# mcu.net
KiCad netlist of a schematic drawn in Altium Designer
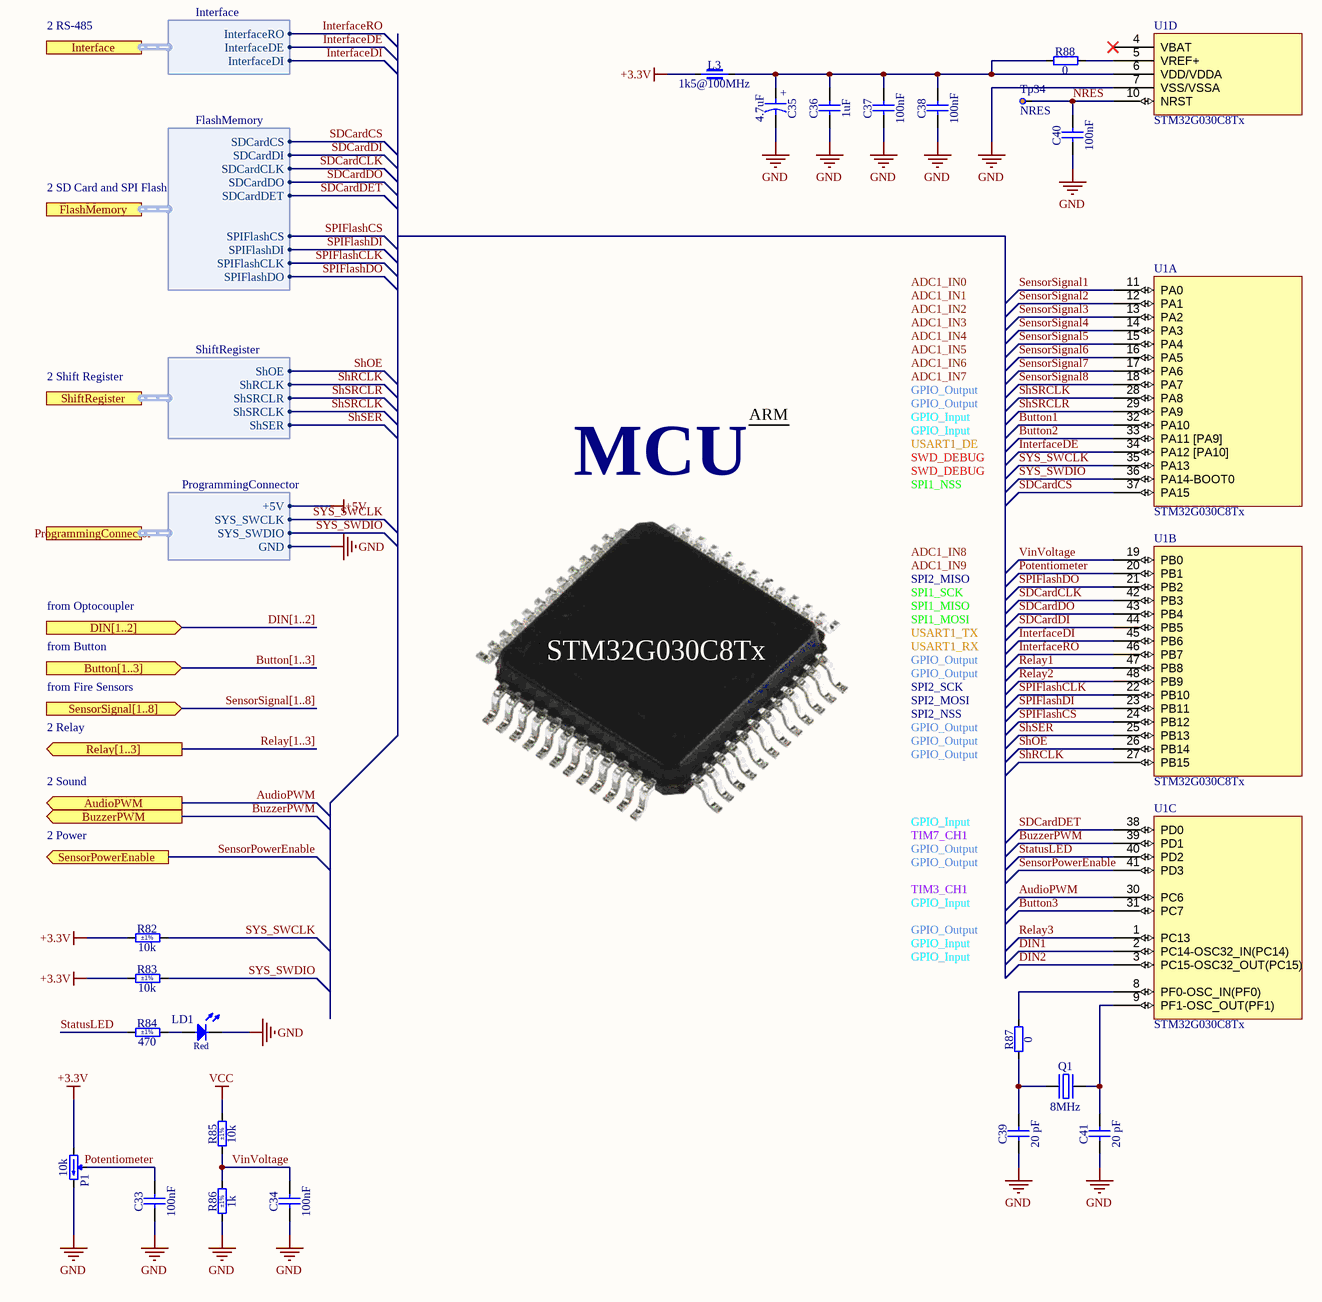
[diagram p0: mcu.SchDoc]

(export (version "E")
  (design (tool "Eeschema 10.0.6"))
  (components
    (comp (ref "C33")
      (value "100nF")
      (footprint "CAPC1608X87N")
      (description "Non-polarised capacitor")
      (fields
        (field (name "PART NUMBER") "CC0603_100NF_50V_10%_X7R")
        (field (name "VOLTAGE") "50V")
        (field (name "AUTHOR") "CERN DEM JLC")
      )
      (libsource (lib "Capacitors") (part "Capacitor - non polarized"))
    )
    (comp (ref "C34")
      (value "100nF")
      (footprint "CAPC1608X87N")
      (description "Non-polarised capacitor")
      (fields
        (field (name "PART NUMBER") "CC0603_100NF_50V_10%_X7R")
        (field (name "VOLTAGE") "50V")
        (field (name "AUTHOR") "CERN DEM JLC")
      )
      (libsource (lib "Capacitors") (part "Capacitor - non polarized"))
    )
    (comp (ref "C35")
      (value "4.7uF")
      (footprint "CAPMP3216X180N")
      (description "Polarised capacitor")
      (fields
        (field (name "PART NUMBER") "CTE3216-18_4.7UF_10V_10%_AVX_TPSA475K010T1400")
        (field (name "VOLTAGE") "10V")
        (field (name "AUTHOR") "CERN DEM JLC")
      )
      (libsource (lib "Capacitors") (part "Capacitor - polarized"))
    )
    (comp (ref "C36")
      (value "1uF")
      (footprint "CAPC1608X87N")
      (description "Non-polarised capacitor")
      (fields
        (field (name "PART NUMBER") "CC0603_1UF_16V_10%_X7R")
        (field (name "VOLTAGE") "16V")
        (field (name "AUTHOR") "CERN DEM JLC")
      )
      (libsource (lib "Capacitors") (part "Capacitor - non polarized"))
    )
    (comp (ref "C37")
      (value "100nF")
      (footprint "CAPC1608X87N")
      (description "Non-polarised capacitor")
      (fields
        (field (name "PART NUMBER") "CC0603_100NF_50V_10%_X7R")
        (field (name "VOLTAGE") "50V")
        (field (name "AUTHOR") "CERN DEM JLC")
      )
      (libsource (lib "Capacitors") (part "Capacitor - non polarized"))
    )
    (comp (ref "C38")
      (value "100nF")
      (footprint "CAPC1608X87N")
      (description "Non-polarised capacitor")
      (fields
        (field (name "PART NUMBER") "CC0603_100NF_50V_10%_X7R")
        (field (name "VOLTAGE") "50V")
        (field (name "AUTHOR") "CERN DEM JLC")
      )
      (libsource (lib "Capacitors") (part "Capacitor - non polarized"))
    )
    (comp (ref "C39")
      (value "20 pF")
      (footprint "CAPC1608X90N")
      (description "Non-polarised capacitor")
      (fields
        (field (name "PART NUMBER") "CC0603_20PF_50V_5%_NP0")
        (field (name "VOLTAGE") "50V")
        (field (name "AUTHOR") "CERN DEM JMW")
      )
      (libsource (lib "Capacitors") (part "Capacitor - non polarized"))
    )
    (comp (ref "C40")
      (value "100nF")
      (footprint "CAPC1608X87N")
      (description "Non-polarised capacitor")
      (fields
        (field (name "PART NUMBER") "CC0603_100NF_50V_10%_X7R")
        (field (name "VOLTAGE") "50V")
        (field (name "AUTHOR") "CERN DEM JLC")
      )
      (libsource (lib "Capacitors") (part "Capacitor - non polarized"))
    )
    (comp (ref "C41")
      (value "20 pF")
      (footprint "CAPC1608X90N")
      (description "Non-polarised capacitor")
      (fields
        (field (name "PART NUMBER") "CC0603_20PF_50V_5%_NP0")
        (field (name "VOLTAGE") "50V")
        (field (name "AUTHOR") "CERN DEM JMW")
      )
      (libsource (lib "Capacitors") (part "Capacitor - non polarized"))
    )
    (comp (ref "L3")
      (value "1k5@100MHz")
      (footprint "INDC2012X110N")
      (fields
        (field (name "PART NUMBER") "IND0805_WURTH_742792097")
        (field (name "POWER") "1A")
        (field (name "TOLERANCE") "±25%")
        (field (name "AUTHOR") "CERN DEM MR")
      )
      (libsource (lib "Inductors & Transformers") (part "Ferrite Bead"))
    )
    (comp (ref "LD1")
      (value "Red")
      (footprint "LED_AVAGO_HSMH-C150")
      (description "LED Red 1C 2A")
      (fields
        (field (name "PART NUMBER") "LED_AVAGO_HSMH-C150")
        (field (name "MANUFACTURER") "AVAGO TECHNOLOGIES")
        (field (name "AUTHOR") "CERN DEM JLC")
      )
      (libsource (lib "ICs And Semiconductors") (part "LED Red 1C 2A"))
    )
    (comp (ref "P1")
      (value "10k")
      (footprint "TRIM_BOURNS_3296W")
      (description "Trimming Potentiometer")
      (fields
        (field (name "PART NUMBER") "TRIM_25T_10K_BOURNS_3296W-1-103LF")
        (field (name "POWER") "0.5W")
        (field (name "AUTHOR") "CERN DEM BC")
      )
      (libsource (lib "Resistors") (part "Trimming Potentiometer"))
    )
    (comp (ref "Q1")
      (value "8MHz")
      (footprint "XTAL_TXC_7A")
      (description "Quartz Crystal")
      (fields
        (field (name "PART NUMBER") "XTAL_8MHZ_TXC_7A-8.000MAAE-T")
        (field (name "MANUFACTURER") "TXC CORPORATION")
        (field (name "AUTHOR") "CERN DEM JLC")
      )
      (libsource (lib "ICs And Semiconductors") (part "Quartz Crystal"))
    )
    (comp (ref "R82")
      (value "10k")
      (footprint "RESC1608X55N")
      (description "Resistor - 1%")
      (fields
        (field (name "TOLERANCE") "±1%")
        (field (name "PART NUMBER") "R0603_10K_1%_0.1W_100PPM")
        (field (name "POWER") "0.1W")
        (field (name "AUTHOR") "CERN DEM JLC")
      )
      (libsource (lib "Resistors") (part "Resistor - 1%"))
    )
    (comp (ref "R83")
      (value "10k")
      (footprint "RESC1608X55N")
      (description "Resistor - 1%")
      (fields
        (field (name "TOLERANCE") "±1%")
        (field (name "PART NUMBER") "R0603_10K_1%_0.1W_100PPM")
        (field (name "POWER") "0.1W")
        (field (name "AUTHOR") "CERN DEM JLC")
      )
      (libsource (lib "Resistors") (part "Resistor - 1%"))
    )
    (comp (ref "R84")
      (value "470")
      (footprint "RESC1608X55N")
      (description "Resistor - 1%")
      (fields
        (field (name "TOLERANCE") "±1%")
        (field (name "PART NUMBER") "R0603_470R_1%_0.1W_100PPM")
        (field (name "POWER") "0.1W")
        (field (name "AUTHOR") "CERN DEM JLC")
      )
      (libsource (lib "Resistors") (part "Resistor - 1%"))
    )
    (comp (ref "R85")
      (value "10k")
      (footprint "RESC1608X55N")
      (description "Resistor - 1%")
      (fields
        (field (name "TOLERANCE") "±1%")
        (field (name "PART NUMBER") "R0603_10K_1%_0.1W_100PPM")
        (field (name "POWER") "0.1W")
        (field (name "AUTHOR") "CERN DEM JLC")
      )
      (libsource (lib "Resistors") (part "Resistor - 1%"))
    )
    (comp (ref "R86")
      (value "1k")
      (footprint "RESC1608X55N")
      (description "Resistor - 1%")
      (fields
        (field (name "TOLERANCE") "±1%")
        (field (name "PART NUMBER") "R0603_1K_1%_0.1W_100PPM")
        (field (name "POWER") "0.1W")
        (field (name "AUTHOR") "CERN DEM JLC")
      )
      (libsource (lib "Resistors") (part "Resistor - 1%"))
    )
    (comp (ref "R87")
      (value "0")
      (footprint "RESC1608X55N")
      (description "Resistor")
      (fields
        (field (name "PART NUMBER") "R0603_0R_JUMPER")
        (field (name "MANUFACTURER") "GENERIC")
        (field (name "AUTHOR") "CERN DEM JLC")
      )
      (libsource (lib "Resistors") (part "Resistor"))
    )
    (comp (ref "R88")
      (value "0")
      (footprint "RESC1608X55N")
      (description "Resistor")
      (fields
        (field (name "PART NUMBER") "R0603_0R_JUMPER")
        (field (name "MANUFACTURER") "GENERIC")
        (field (name "AUTHOR") "CERN DEM JLC")
      )
      (libsource (lib "Resistors") (part "Resistor"))
    )
    (comp (ref "Tp34")
      (value "NRES")
      (footprint "fromST:TP_C40")
      (description "Test point")
      (fields (field (name "PUBLISHER") "Altium Limited"))
      (libsource (lib "Sajad_Altium_Library") (part "Test point"))
    )
    (comp (ref "U1")
      (value "STM32G030C8Tx")
      (footprint "PCB - LEADLESS - LQFP - ST LQFP-48 7X7MM:ST LQFP-48 7x7MM")
      (libsource (lib "STM32G030C8Tx") (part "STM32G030C8Tx"))
    )
  )
  (nets
    (net (code "5") (name "+3.3V") (class "Default")
      (node (ref "L3") (pin "1") (pinfunction "1_1") (pintype "passive"))
      (node (ref "P1") (pin "1") (pinfunction "CCW_1") (pintype "passive"))
      (node (ref "R82") (pin "1") (pinfunction "1_1") (pintype "passive"))
      (node (ref "R83") (pin "1") (pinfunction "1_1") (pintype "passive"))
    )
    (net (code "7") (name "/AudioPWM") (class "Default")
      (node (ref "U1") (pin "30") (pinfunction "PC6_30") (pintype "bidirectional"))
    )
    (net (code "8") (name "/Button1") (class "Default")
      (node (ref "U1") (pin "32") (pinfunction "PA10_32") (pintype "bidirectional"))
    )
    (net (code "9") (name "/Button2") (class "Default")
      (node (ref "U1") (pin "33") (pinfunction "PA11_[PA9]_33") (pintype "bidirectional"))
    )
    (net (code "10") (name "/Button3") (class "Default")
      (node (ref "U1") (pin "31") (pinfunction "PC7_31") (pintype "bidirectional"))
    )
    (net (code "12") (name "/BuzzerPWM") (class "Default")
      (node (ref "U1") (pin "39") (pinfunction "PD1_39") (pintype "bidirectional"))
    )
    (net (code "13") (name "/DIN1") (class "Default")
      (node (ref "U1") (pin "2") (pinfunction "PC14-OSC32_IN(PC14)_2") (pintype "bidirectional"))
    )
    (net (code "14") (name "/DIN2") (class "Default")
      (node (ref "U1") (pin "3") (pinfunction "PC15-OSC32_OUT(PC15)_3") (pintype "bidirectional"))
    )
    (net (code "16") (name "/InterfaceDE") (class "Default")
      (node (ref "U1") (pin "34") (pinfunction "PA12_[PA10]_34") (pintype "bidirectional"))
    )
    (net (code "17") (name "/InterfaceDI") (class "Default")
      (node (ref "U1") (pin "45") (pinfunction "PB6_45") (pintype "bidirectional"))
    )
    (net (code "18") (name "/InterfaceRO") (class "Default")
      (node (ref "U1") (pin "46") (pinfunction "PB7_46") (pintype "bidirectional"))
    )
    (net (code "19") (name "/NRES") (class "Default")
      (node (ref "C40") (pin "2") (pinfunction "2_2") (pintype "passive"))
      (node (ref "Tp34") (pin "1") (pinfunction "1_1") (pintype "passive"))
      (node (ref "U1") (pin "10") (pinfunction "NRST_10") (pintype "bidirectional"))
    )
    (net (code "20") (name "/Potentiometer") (class "Default")
      (node (ref "C33") (pin "2") (pinfunction "2_2") (pintype "passive"))
      (node (ref "P1") (pin "2") (pinfunction "W_2") (pintype "passive"))
      (node (ref "U1") (pin "20") (pinfunction "PB1_20") (pintype "bidirectional"))
    )
    (net (code "21") (name "/Relay1") (class "Default")
      (node (ref "U1") (pin "47") (pinfunction "PB8_47") (pintype "bidirectional"))
    )
    (net (code "22") (name "/Relay2") (class "Default")
      (node (ref "U1") (pin "48") (pinfunction "PB9_48") (pintype "bidirectional"))
    )
    (net (code "23") (name "/Relay3") (class "Default")
      (node (ref "U1") (pin "1") (pinfunction "PC13_1") (pintype "bidirectional"))
    )
    (net (code "25") (name "/SDCardCLK") (class "Default")
      (node (ref "U1") (pin "42") (pinfunction "PB3_42") (pintype "bidirectional"))
    )
    (net (code "26") (name "/SDCardCS") (class "Default")
      (node (ref "U1") (pin "37") (pinfunction "PA15_37") (pintype "bidirectional"))
    )
    (net (code "27") (name "/SDCardDET") (class "Default")
      (node (ref "U1") (pin "38") (pinfunction "PD0_38") (pintype "bidirectional"))
    )
    (net (code "28") (name "/SDCardDI") (class "Default")
      (node (ref "U1") (pin "44") (pinfunction "PB5_44") (pintype "bidirectional"))
    )
    (net (code "29") (name "/SDCardDO") (class "Default")
      (node (ref "U1") (pin "43") (pinfunction "PB4_43") (pintype "bidirectional"))
    )
    (net (code "30") (name "/SPIFlashCLK") (class "Default")
      (node (ref "U1") (pin "22") (pinfunction "PB10_22") (pintype "bidirectional"))
    )
    (net (code "31") (name "/SPIFlashCS") (class "Default")
      (node (ref "U1") (pin "24") (pinfunction "PB12_24") (pintype "bidirectional"))
    )
    (net (code "32") (name "/SPIFlashDI") (class "Default")
      (node (ref "U1") (pin "23") (pinfunction "PB11_23") (pintype "bidirectional"))
    )
    (net (code "33") (name "/SPIFlashDO") (class "Default")
      (node (ref "U1") (pin "21") (pinfunction "PB2_21") (pintype "bidirectional"))
    )
    (net (code "34") (name "/SYS_SWCLK") (class "Default")
      (node (ref "R82") (pin "2") (pinfunction "2_2") (pintype "passive"))
      (node (ref "U1") (pin "35") (pinfunction "PA13_35") (pintype "bidirectional"))
    )
    (net (code "35") (name "/SYS_SWDIO") (class "Default")
      (node (ref "R83") (pin "2") (pinfunction "2_2") (pintype "passive"))
      (node (ref "U1") (pin "36") (pinfunction "PA14-BOOT0_36") (pintype "bidirectional"))
    )
    (net (code "36") (name "/SensorPowerEnable") (class "Default")
      (node (ref "U1") (pin "41") (pinfunction "PD3_41") (pintype "bidirectional"))
    )
    (net (code "37") (name "/SensorSignal1") (class "Default")
      (node (ref "U1") (pin "11") (pinfunction "PA0_11") (pintype "bidirectional"))
    )
    (net (code "38") (name "/SensorSignal2") (class "Default")
      (node (ref "U1") (pin "12") (pinfunction "PA1_12") (pintype "bidirectional"))
    )
    (net (code "39") (name "/SensorSignal3") (class "Default")
      (node (ref "U1") (pin "13") (pinfunction "PA2_13") (pintype "bidirectional"))
    )
    (net (code "40") (name "/SensorSignal4") (class "Default")
      (node (ref "U1") (pin "14") (pinfunction "PA3_14") (pintype "bidirectional"))
    )
    (net (code "41") (name "/SensorSignal5") (class "Default")
      (node (ref "U1") (pin "15") (pinfunction "PA4_15") (pintype "bidirectional"))
    )
    (net (code "42") (name "/SensorSignal6") (class "Default")
      (node (ref "U1") (pin "16") (pinfunction "PA5_16") (pintype "bidirectional"))
    )
    (net (code "43") (name "/SensorSignal7") (class "Default")
      (node (ref "U1") (pin "17") (pinfunction "PA6_17") (pintype "bidirectional"))
    )
    (net (code "44") (name "/SensorSignal8") (class "Default")
      (node (ref "U1") (pin "18") (pinfunction "PA7_18") (pintype "bidirectional"))
    )
    (net (code "46") (name "/ShOE") (class "Default")
      (node (ref "U1") (pin "26") (pinfunction "PB14_26") (pintype "bidirectional"))
    )
    (net (code "47") (name "/ShRCLK") (class "Default")
      (node (ref "U1") (pin "27") (pinfunction "PB15_27") (pintype "bidirectional"))
    )
    (net (code "48") (name "/ShSER") (class "Default")
      (node (ref "U1") (pin "25") (pinfunction "PB13_25") (pintype "bidirectional"))
    )
    (net (code "49") (name "/ShSRCLK") (class "Default")
      (node (ref "U1") (pin "28") (pinfunction "PA8_28") (pintype "bidirectional"))
    )
    (net (code "50") (name "/ShSRCLR") (class "Default")
      (node (ref "U1") (pin "29") (pinfunction "PA9_29") (pintype "bidirectional"))
    )
    (net (code "51") (name "/StatusLED") (class "Default")
      (node (ref "R84") (pin "1") (pinfunction "1_1") (pintype "passive"))
      (node (ref "U1") (pin "40") (pinfunction "PD2_40") (pintype "bidirectional"))
    )
    (net (code "52") (name "/VinVoltage") (class "Default")
      (node (ref "C34") (pin "2") (pinfunction "2_2") (pintype "passive"))
      (node (ref "R85") (pin "1") (pinfunction "1_1") (pintype "passive"))
      (node (ref "R86") (pin "2") (pinfunction "2_2") (pintype "passive"))
      (node (ref "U1") (pin "19") (pinfunction "PB0_19") (pintype "bidirectional"))
    )
    (net (code "57") (name "GND") (class "Default")
      (node (ref "C33") (pin "1") (pinfunction "1_1") (pintype "passive"))
      (node (ref "C34") (pin "1") (pinfunction "1_1") (pintype "passive"))
      (node (ref "C35") (pin "2") (pinfunction "2_2") (pintype "passive"))
      (node (ref "C36") (pin "1") (pinfunction "1_1") (pintype "passive"))
      (node (ref "C37") (pin "1") (pinfunction "1_1") (pintype "passive"))
      (node (ref "C38") (pin "1") (pinfunction "1_1") (pintype "passive"))
      (node (ref "C39") (pin "1") (pinfunction "1_1") (pintype "passive"))
      (node (ref "C40") (pin "1") (pinfunction "1_1") (pintype "passive"))
      (node (ref "C41") (pin "1") (pinfunction "1_1") (pintype "passive"))
      (node (ref "LD1") (pin "1") (pinfunction "C_1") (pintype "passive"))
      (node (ref "P1") (pin "3") (pinfunction "CW_3") (pintype "passive"))
      (node (ref "R86") (pin "1") (pinfunction "1_1") (pintype "passive"))
      (node (ref "U1") (pin "7") (pinfunction "VSS/VSSA_7") (pintype "power_in"))
    )
    (net (code "58") (name "Net-(LD1-A)") (class "Default")
      (node (ref "LD1") (pin "2") (pinfunction "A_2") (pintype "passive"))
      (node (ref "R84") (pin "2") (pinfunction "2_2") (pintype "passive"))
    )
    (net (code "59") (name "Net-(Q1-OSC1)") (class "Default")
      (node (ref "C39") (pin "2") (pinfunction "2_2") (pintype "passive"))
      (node (ref "Q1") (pin "1") (pinfunction "OSC1_1") (pintype "passive"))
      (node (ref "R87") (pin "1") (pinfunction "1_1") (pintype "passive"))
    )
    (net (code "60") (name "Net-(Q1-OSC2)") (class "Default")
      (node (ref "C41") (pin "2") (pinfunction "2_2") (pintype "passive"))
      (node (ref "Q1") (pin "2") (pinfunction "OSC2_2") (pintype "passive"))
      (node (ref "U1") (pin "9") (pinfunction "PF1-OSC_OUT(PF1)_9") (pintype "bidirectional"))
    )
    (net (code "61") (name "Net-(U1C-PF0-OSC_IN(PF0))") (class "Default")
      (node (ref "R87") (pin "2") (pinfunction "2_2") (pintype "passive"))
      (node (ref "U1") (pin "8") (pinfunction "PF0-OSC_IN(PF0)_8") (pintype "bidirectional"))
    )
    (net (code "62") (name "Net-(U1D-VDD{slash}VDDA)") (class "Default")
      (node (ref "C35") (pin "1") (pinfunction "1_1") (pintype "passive"))
      (node (ref "C36") (pin "2") (pinfunction "2_2") (pintype "passive"))
      (node (ref "C37") (pin "2") (pinfunction "2_2") (pintype "passive"))
      (node (ref "C38") (pin "2") (pinfunction "2_2") (pintype "passive"))
      (node (ref "L3") (pin "2") (pinfunction "2_2") (pintype "passive"))
      (node (ref "R88") (pin "1") (pinfunction "1_1") (pintype "passive"))
      (node (ref "U1") (pin "6") (pinfunction "VDD/VDDA_6") (pintype "power_in"))
    )
    (net (code "63") (name "Net-(U1D-VREF+)") (class "Default")
      (node (ref "R88") (pin "2") (pinfunction "2_2") (pintype "passive"))
      (node (ref "U1") (pin "5") (pinfunction "VREF+_5") (pintype "power_in"))
    )
    (net (code "64") (name "VCC") (class "Default")
      (node (ref "R85") (pin "2") (pinfunction "2_2") (pintype "passive"))
    )
    (net (code "65") (name "unconnected-(U1D-VBAT-Pad4)") (class "Default")
      (node (ref "U1") (pin "4") (pinfunction "VBAT_4") (pintype "power_in+no_connect"))
    )
  )
)
